# eink-type1.net
KiCad netlist of a schematic drawn in EAGLE
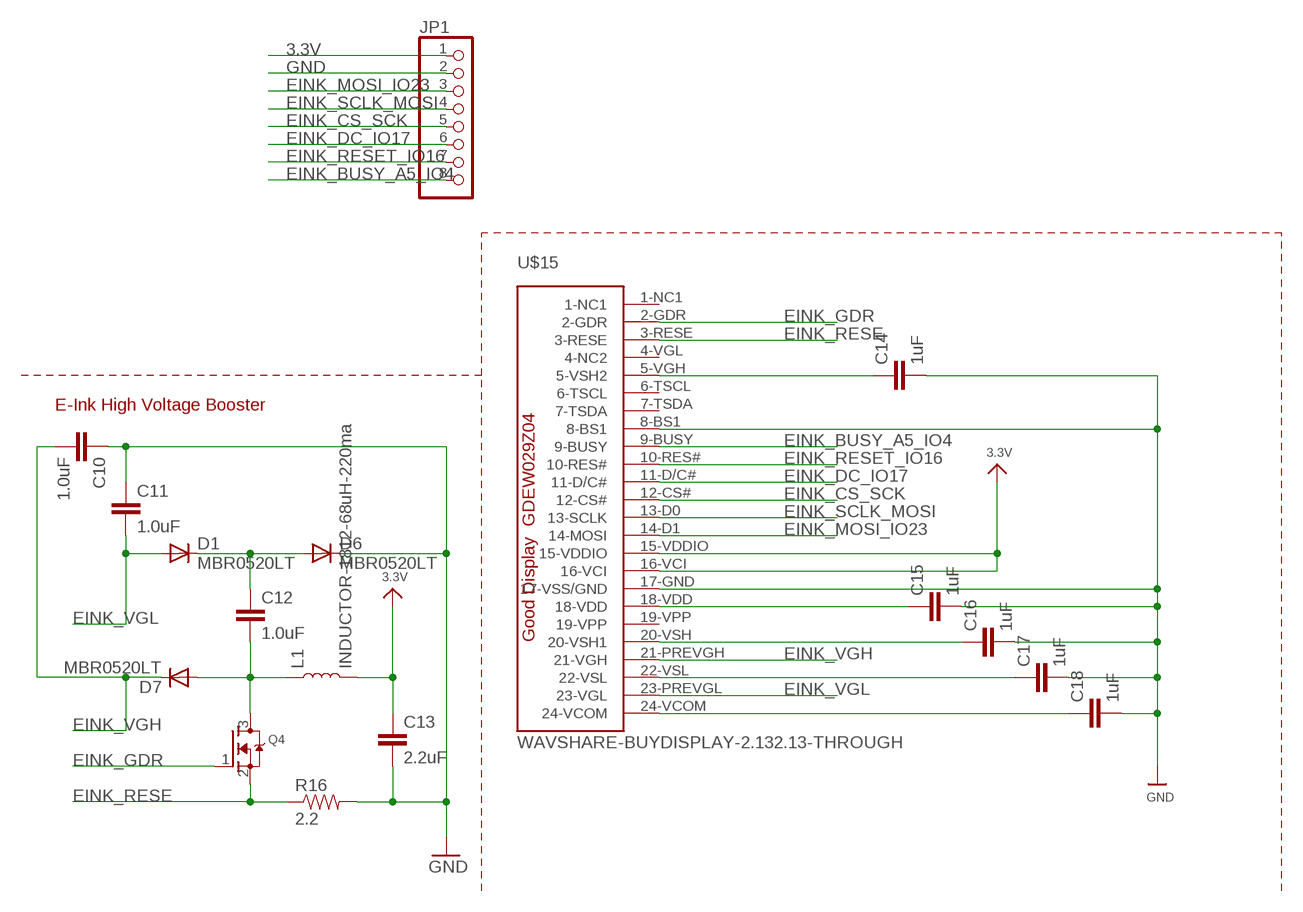
[diagram p0: schematic, sheet 1]

(export (version "E")
  (design (tool "Eeschema 10.0.6"))
  (components
    (comp (ref "C10")
      (value "1.0uF")
      (footprint "eagle-import:0603")
      (libsource (lib "eagle-import") (part "1.0UF-0603-16V-10%"))
    )
    (comp (ref "C11")
      (value "1.0uF")
      (footprint "eagle-import:0603")
      (libsource (lib "eagle-import") (part "1.0UF-0603-16V-10%"))
    )
    (comp (ref "C12")
      (value "1.0uF")
      (footprint "eagle-import:0603")
      (libsource (lib "eagle-import") (part "1.0UF-0603-16V-10%"))
    )
    (comp (ref "C13")
      (value "2.2uF")
      (footprint "eagle-import:0603")
      (libsource (lib "eagle-import") (part "2.2UF-0603-10V-20%"))
    )
    (comp (ref "C14")
      (value "1uF")
      (footprint "eagle-import:0603-CAP")
      (libsource (lib "eagle-import") (part "0.1UF-25V-5%(0603)"))
    )
    (comp (ref "C15")
      (value "1uF")
      (footprint "eagle-import:0603-CAP")
      (libsource (lib "eagle-import") (part "0.1UF-25V-5%(0603)"))
    )
    (comp (ref "C16")
      (value "1uF")
      (footprint "eagle-import:0603-CAP")
      (libsource (lib "eagle-import") (part "0.1UF-25V-5%(0603)"))
    )
    (comp (ref "C17")
      (value "1uF")
      (footprint "eagle-import:0603-CAP")
      (libsource (lib "eagle-import") (part "0.1UF-25V-5%(0603)"))
    )
    (comp (ref "C18")
      (value "1uF")
      (footprint "eagle-import:0603-CAP")
      (libsource (lib "eagle-import") (part "0.1UF-25V-5%(0603)"))
    )
    (comp (ref "D1")
      (value "MBR0520LT")
      (footprint "eagle-import:SOD123")
      (libsource (lib "eagle-import") (part "MBR0520LT"))
    )
    (comp (ref "D6")
      (value "MBR0520LT")
      (footprint "eagle-import:SOD123")
      (libsource (lib "eagle-import") (part "MBR0520LT"))
    )
    (comp (ref "D7")
      (value "MBR0520LT")
      (footprint "eagle-import:SOD123")
      (libsource (lib "eagle-import") (part "MBR0520LT"))
    )
    (comp (ref "JP1")
      (value "PINHD-1X8")
      (footprint "eagle-import:1X08")
      (libsource (lib "eagle-import") (part "PINHD-1X8"))
    )
    (comp (ref "L1")
      (value "INDUCTOR-1812-68uH-220ma")
      (footprint "eagle-import:1812")
      (libsource (lib "eagle-import") (part "INDUCTOR-1812"))
    )
    (comp (ref "Q4")
      (value "MOSFET-NREFLOW")
      (footprint "eagle-import:SOT23")
      (libsource (lib "eagle-import") (part "MOSFET-NREFLOW"))
    )
    (comp (ref "R16")
      (value "2.2")
      (footprint "eagle-import:0603-RES")
      (libsource (lib "eagle-import") (part "4.7KOHM-1/10W-1%(0603)"))
    )
    (comp (ref "U$15")
      (value "WAVSHARE-BUYDISPLAY-2.132.13-THROUGH")
      (footprint "eagle-import:WAVSHARE-BUYDISPLAY-2.13-THM")
      (libsource (lib "eagle-import") (part "WAVSHARE-BUYDISPLAY-2.132.13-THROUGH"))
    )
  )
  (nets
    (net (code "1") (name "/EINK_BUSY_A5_IO4") (class "Default")
      (node (ref "JP1") (pin "8") (pinfunction "8_8") (pintype "passive"))
      (node (ref "U$15") (pin "9-BUSY") (pinfunction "9-BUSY_9-BUSY") (pintype "bidirectional"))
    )
    (net (code "2") (name "/EINK_CS_SCK") (class "Default")
      (node (ref "JP1") (pin "5") (pinfunction "5_5") (pintype "passive"))
      (node (ref "U$15") (pin "12-CS#") (pinfunction "12-CS#_12-CS#") (pintype "bidirectional"))
    )
    (net (code "3") (name "/EINK_DC_IO17") (class "Default")
      (node (ref "JP1") (pin "6") (pinfunction "6_6") (pintype "passive"))
      (node (ref "U$15") (pin "11-D/C#") (pinfunction "11-D/C#_11-D/C#") (pintype "bidirectional"))
    )
    (net (code "4") (name "/EINK_GDR") (class "Default")
      (node (ref "Q4") (pin "1") (pinfunction "G_1") (pintype "bidirectional"))
      (node (ref "U$15") (pin "2-GDR") (pinfunction "2-GDR_2-GDR") (pintype "bidirectional"))
    )
    (net (code "5") (name "/EINK_MOSI_IO23") (class "Default")
      (node (ref "JP1") (pin "3") (pinfunction "3_3") (pintype "passive"))
      (node (ref "U$15") (pin "14-D1") (pinfunction "14-MOSI_14-D1") (pintype "bidirectional"))
    )
    (net (code "6") (name "/EINK_RESE") (class "Default")
      (node (ref "Q4") (pin "2") (pinfunction "S_2") (pintype "bidirectional"))
      (node (ref "R16") (pin "1") (pinfunction "1_1") (pintype "passive"))
      (node (ref "U$15") (pin "3-RESE") (pinfunction "3-RESE_3-RESE") (pintype "bidirectional"))
    )
    (net (code "7") (name "/EINK_RESET_IO16") (class "Default")
      (node (ref "JP1") (pin "7") (pinfunction "7_7") (pintype "passive"))
      (node (ref "U$15") (pin "10-RES#") (pinfunction "10-RES#_10-RES#") (pintype "bidirectional"))
    )
    (net (code "8") (name "/EINK_SCLK_MOSI") (class "Default")
      (node (ref "JP1") (pin "4") (pinfunction "4_4") (pintype "passive"))
      (node (ref "U$15") (pin "13-D0") (pinfunction "13-SCLK_13-D0") (pintype "bidirectional"))
    )
    (net (code "9") (name "/EINK_VGH") (class "Default")
      (node (ref "C10") (pin "2") (pinfunction "2_2") (pintype "passive"))
      (node (ref "D7") (pin "C") (pinfunction "C_C") (pintype "passive"))
      (node (ref "U$15") (pin "21-PREVGH") (pinfunction "21-VGH_21-PREVGH") (pintype "bidirectional"))
    )
    (net (code "10") (name "/EINK_VGL") (class "Default")
      (node (ref "C11") (pin "2") (pinfunction "2_2") (pintype "passive"))
      (node (ref "D1") (pin "A") (pinfunction "A_A") (pintype "passive"))
      (node (ref "U$15") (pin "23-PREVGL") (pinfunction "23-VGL_23-PREVGL") (pintype "bidirectional"))
    )
    (net (code "11") (name "3.3V") (class "Default")
      (node (ref "C13") (pin "1") (pinfunction "1_1") (pintype "passive"))
      (node (ref "JP1") (pin "1") (pinfunction "1_1") (pintype "passive"))
      (node (ref "L1") (pin "2") (pinfunction "2_2") (pintype "passive"))
      (node (ref "U$15") (pin "15-VDDIO") (pinfunction "15-VDDIO_15-VDDIO") (pintype "bidirectional"))
      (node (ref "U$15") (pin "16-VCI") (pinfunction "16-VCI_16-VCI") (pintype "bidirectional"))
    )
    (net (code "12") (name "GND") (class "Default")
      (node (ref "C10") (pin "1") (pinfunction "1_1") (pintype "passive"))
      (node (ref "C11") (pin "1") (pinfunction "1_1") (pintype "passive"))
      (node (ref "C13") (pin "2") (pinfunction "2_2") (pintype "passive"))
      (node (ref "C14") (pin "2") (pinfunction "2_2") (pintype "passive"))
      (node (ref "C15") (pin "2") (pinfunction "2_2") (pintype "passive"))
      (node (ref "C16") (pin "2") (pinfunction "2_2") (pintype "passive"))
      (node (ref "C17") (pin "2") (pinfunction "2_2") (pintype "passive"))
      (node (ref "C18") (pin "2") (pinfunction "2_2") (pintype "passive"))
      (node (ref "D6") (pin "C") (pinfunction "C_C") (pintype "passive"))
      (node (ref "JP1") (pin "2") (pinfunction "2_2") (pintype "passive"))
      (node (ref "R16") (pin "2") (pinfunction "2_2") (pintype "passive"))
      (node (ref "U$15") (pin "17-GND") (pinfunction "17-VSS/GND_17-GND") (pintype "bidirectional"))
      (node (ref "U$15") (pin "8-BS1") (pinfunction "8-BS1_8-BS1") (pintype "bidirectional"))
    )
    (net (code "13") (name "Net-(C12-Pad1)") (class "Default")
      (node (ref "C12") (pin "1") (pinfunction "1_1") (pintype "passive"))
      (node (ref "D1") (pin "C") (pinfunction "C_C") (pintype "passive"))
      (node (ref "D6") (pin "A") (pinfunction "A_A") (pintype "passive"))
    )
    (net (code "14") (name "Net-(C15-Pad1)") (class "Default")
      (node (ref "C15") (pin "1") (pinfunction "1_1") (pintype "passive"))
      (node (ref "U$15") (pin "18-VDD") (pinfunction "18-VDD_18-VDD") (pintype "bidirectional"))
    )
    (net (code "15") (name "Net-(C17-Pad1)") (class "Default")
      (node (ref "C17") (pin "1") (pinfunction "1_1") (pintype "passive"))
      (node (ref "U$15") (pin "22-VSL") (pinfunction "22-VSL_22-VSL") (pintype "bidirectional"))
    )
    (net (code "16") (name "Net-(C18-Pad1)") (class "Default")
      (node (ref "C18") (pin "1") (pinfunction "1_1") (pintype "passive"))
      (node (ref "U$15") (pin "24-VCOM") (pinfunction "24-VCOM_24-VCOM") (pintype "bidirectional"))
    )
    (net (code "17") (name "Net-(Q4-D)") (class "Default")
      (node (ref "C12") (pin "2") (pinfunction "2_2") (pintype "passive"))
      (node (ref "D7") (pin "A") (pinfunction "A_A") (pintype "passive"))
      (node (ref "L1") (pin "1") (pinfunction "1_1") (pintype "passive"))
      (node (ref "Q4") (pin "3") (pinfunction "D_3") (pintype "bidirectional"))
    )
    (net (code "18") (name "Net-(U$15-5-VSH2)") (class "Default")
      (node (ref "C14") (pin "1") (pinfunction "1_1") (pintype "passive"))
      (node (ref "U$15") (pin "5-VGH") (pinfunction "5-VSH2_5-VGH") (pintype "bidirectional"))
    )
    (net (code "19") (name "Net-(U$15-20-VSH1)") (class "Default")
      (node (ref "C16") (pin "1") (pinfunction "1_1") (pintype "passive"))
      (node (ref "U$15") (pin "20-VSH") (pinfunction "20-VSH1_20-VSH") (pintype "bidirectional"))
    )
    (net (code "20") (name "unconnected-(U$15-4-NC2-Pad4-VGL)") (class "Default")
      (node (ref "U$15") (pin "4-VGL") (pinfunction "4-NC2_4-VGL") (pintype "bidirectional"))
    )
    (net (code "21") (name "unconnected-(U$15-Pad1-NC1)") (class "Default")
      (node (ref "U$15") (pin "1-NC1") (pinfunction "1-NC1_1-NC1") (pintype "bidirectional"))
    )
    (net (code "22") (name "unconnected-(U$15-Pad6-TSCL)") (class "Default")
      (node (ref "U$15") (pin "6-TSCL") (pinfunction "6-TSCL_6-TSCL") (pintype "bidirectional"))
    )
    (net (code "23") (name "unconnected-(U$15-Pad7-TSDA)") (class "Default")
      (node (ref "U$15") (pin "7-TSDA") (pinfunction "7-TSDA_7-TSDA") (pintype "bidirectional"))
    )
    (net (code "24") (name "unconnected-(U$15-Pad19-VPP)") (class "Default")
      (node (ref "U$15") (pin "19-VPP") (pinfunction "19-VPP_19-VPP") (pintype "bidirectional"))
    )
  )
)
